# tinyblick.net
KiCad netlist of a schematic drawn in EAGLE
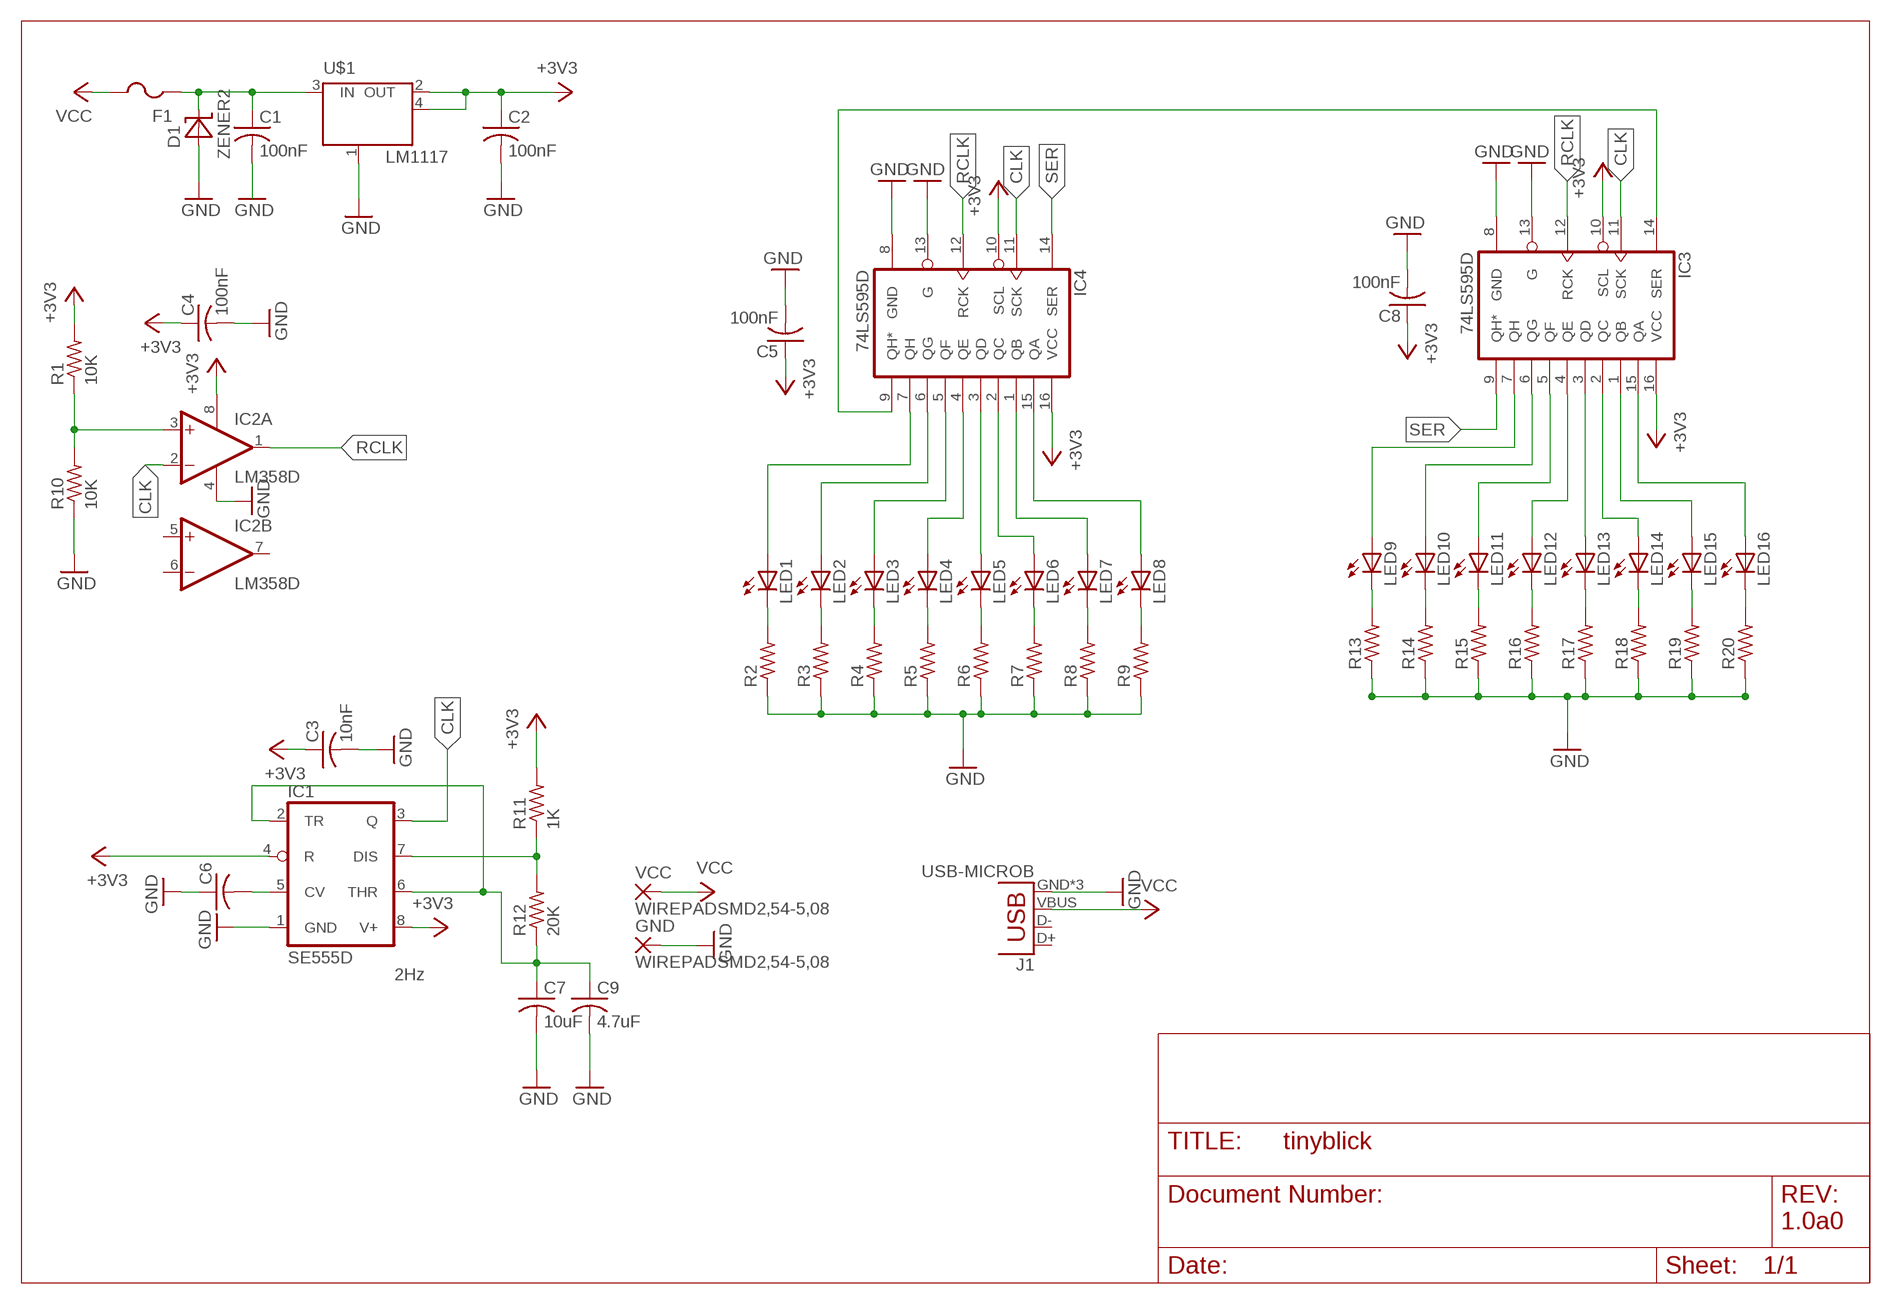
[diagram p0: schematic, sheet 1]

(export (version "E")
  (design (tool "Eeschema 10.0.6"))
  (components
    (comp (ref "C1")
      (value "100nF")
      (footprint "eagle-import:C0603")
      (libsource (lib "eagle-import") (part "C-USC0603"))
    )
    (comp (ref "C2")
      (value "100nF")
      (footprint "eagle-import:C0603")
      (libsource (lib "eagle-import") (part "C-USC0603"))
    )
    (comp (ref "C3")
      (value "10nF")
      (footprint "eagle-import:C0603")
      (libsource (lib "eagle-import") (part "C-USC0603"))
    )
    (comp (ref "C4")
      (value "100nF")
      (footprint "eagle-import:C0603")
      (libsource (lib "eagle-import") (part "C-USC0603"))
    )
    (comp (ref "C5")
      (value "100nF")
      (footprint "eagle-import:C0603")
      (libsource (lib "eagle-import") (part "C-USC0603"))
    )
    (comp (ref "C6")
      (value "C-USC0603")
      (footprint "eagle-import:C0603")
      (libsource (lib "eagle-import") (part "C-USC0603"))
    )
    (comp (ref "C7")
      (value "10uF")
      (footprint "eagle-import:C0603")
      (libsource (lib "eagle-import") (part "C-USC0603"))
    )
    (comp (ref "C8")
      (value "100nF")
      (footprint "eagle-import:C0603")
      (libsource (lib "eagle-import") (part "C-USC0603"))
    )
    (comp (ref "C9")
      (value "4.7uF")
      (footprint "eagle-import:C0603")
      (libsource (lib "eagle-import") (part "C-USC0603"))
    )
    (comp (ref "D1")
      (value "ZENER2")
      (footprint "eagle-import:SOD123")
      (libsource (lib "eagle-import") (part "ZENER2"))
    )
    (comp (ref "F1")
      (value "PTCFUSE-1206")
      (footprint "eagle-import:R1206")
      (libsource (lib "eagle-import") (part "PTCFUSE-1206"))
    )
    (comp (ref "GND")
      (value "WIREPADSMD2,54-5,08")
      (footprint "eagle-import:SMD2,54-5,08")
      (libsource (lib "eagle-import") (part "WIREPADSMD2,54-5,08"))
    )
    (comp (ref "IC1")
      (value "SE555D")
      (footprint "eagle-import:SO08")
      (libsource (lib "eagle-import") (part "555DSE"))
    )
    (comp (ref "IC2")
      (value "LM358D")
      (footprint "eagle-import:SO08")
      (libsource (lib "eagle-import") (part "LM358D"))
    )
    (comp (ref "IC3")
      (value "74LS595D")
      (footprint "eagle-import:SO16")
      (libsource (lib "eagle-import") (part "74595DLS"))
    )
    (comp (ref "IC4")
      (value "74LS595D")
      (footprint "eagle-import:SO16")
      (libsource (lib "eagle-import") (part "74595DLS"))
    )
    (comp (ref "J1")
      (value "USB-MICROB")
      (footprint "eagle-import:USB-MICROB")
      (libsource (lib "eagle-import") (part "USB-MICROB"))
    )
    (comp (ref "LED1")
      (value "LEDCHIP-LED0603")
      (footprint "eagle-import:CHIP-LED0603")
      (libsource (lib "eagle-import") (part "LEDCHIP-LED0603"))
    )
    (comp (ref "LED2")
      (value "LEDCHIP-LED0603")
      (footprint "eagle-import:CHIP-LED0603")
      (libsource (lib "eagle-import") (part "LEDCHIP-LED0603"))
    )
    (comp (ref "LED3")
      (value "LEDCHIP-LED0603")
      (footprint "eagle-import:CHIP-LED0603")
      (libsource (lib "eagle-import") (part "LEDCHIP-LED0603"))
    )
    (comp (ref "LED4")
      (value "LEDCHIP-LED0603")
      (footprint "eagle-import:CHIP-LED0603")
      (libsource (lib "eagle-import") (part "LEDCHIP-LED0603"))
    )
    (comp (ref "LED5")
      (value "LEDCHIP-LED0603")
      (footprint "eagle-import:CHIP-LED0603")
      (libsource (lib "eagle-import") (part "LEDCHIP-LED0603"))
    )
    (comp (ref "LED6")
      (value "LEDCHIP-LED0603")
      (footprint "eagle-import:CHIP-LED0603")
      (libsource (lib "eagle-import") (part "LEDCHIP-LED0603"))
    )
    (comp (ref "LED7")
      (value "LEDCHIP-LED0603")
      (footprint "eagle-import:CHIP-LED0603")
      (libsource (lib "eagle-import") (part "LEDCHIP-LED0603"))
    )
    (comp (ref "LED8")
      (value "LEDCHIP-LED0603")
      (footprint "eagle-import:CHIP-LED0603")
      (libsource (lib "eagle-import") (part "LEDCHIP-LED0603"))
    )
    (comp (ref "LED9")
      (value "LEDCHIP-LED0603")
      (footprint "eagle-import:CHIP-LED0603")
      (libsource (lib "eagle-import") (part "LEDCHIP-LED0603"))
    )
    (comp (ref "LED10")
      (value "LEDCHIP-LED0603")
      (footprint "eagle-import:CHIP-LED0603")
      (libsource (lib "eagle-import") (part "LEDCHIP-LED0603"))
    )
    (comp (ref "LED11")
      (value "LEDCHIP-LED0603")
      (footprint "eagle-import:CHIP-LED0603")
      (libsource (lib "eagle-import") (part "LEDCHIP-LED0603"))
    )
    (comp (ref "LED12")
      (value "LEDCHIP-LED0603")
      (footprint "eagle-import:CHIP-LED0603")
      (libsource (lib "eagle-import") (part "LEDCHIP-LED0603"))
    )
    (comp (ref "LED13")
      (value "LEDCHIP-LED0603")
      (footprint "eagle-import:CHIP-LED0603")
      (libsource (lib "eagle-import") (part "LEDCHIP-LED0603"))
    )
    (comp (ref "LED14")
      (value "LEDCHIP-LED0603")
      (footprint "eagle-import:CHIP-LED0603")
      (libsource (lib "eagle-import") (part "LEDCHIP-LED0603"))
    )
    (comp (ref "LED15")
      (value "LEDCHIP-LED0603")
      (footprint "eagle-import:CHIP-LED0603")
      (libsource (lib "eagle-import") (part "LEDCHIP-LED0603"))
    )
    (comp (ref "LED16")
      (value "LEDCHIP-LED0603")
      (footprint "eagle-import:CHIP-LED0603")
      (libsource (lib "eagle-import") (part "LEDCHIP-LED0603"))
    )
    (comp (ref "R1")
      (value "10K")
      (footprint "eagle-import:R0603")
      (libsource (lib "eagle-import") (part "R-US_R0603"))
    )
    (comp (ref "R2")
      (value "R-US_R0603")
      (footprint "eagle-import:R0603")
      (libsource (lib "eagle-import") (part "R-US_R0603"))
    )
    (comp (ref "R3")
      (value "R-US_R0603")
      (footprint "eagle-import:R0603")
      (libsource (lib "eagle-import") (part "R-US_R0603"))
    )
    (comp (ref "R4")
      (value "R-US_R0603")
      (footprint "eagle-import:R0603")
      (libsource (lib "eagle-import") (part "R-US_R0603"))
    )
    (comp (ref "R5")
      (value "R-US_R0603")
      (footprint "eagle-import:R0603")
      (libsource (lib "eagle-import") (part "R-US_R0603"))
    )
    (comp (ref "R6")
      (value "R-US_R0603")
      (footprint "eagle-import:R0603")
      (libsource (lib "eagle-import") (part "R-US_R0603"))
    )
    (comp (ref "R7")
      (value "R-US_R0603")
      (footprint "eagle-import:R0603")
      (libsource (lib "eagle-import") (part "R-US_R0603"))
    )
    (comp (ref "R8")
      (value "R-US_R0603")
      (footprint "eagle-import:R0603")
      (libsource (lib "eagle-import") (part "R-US_R0603"))
    )
    (comp (ref "R9")
      (value "R-US_R0603")
      (footprint "eagle-import:R0603")
      (libsource (lib "eagle-import") (part "R-US_R0603"))
    )
    (comp (ref "R10")
      (value "10K")
      (footprint "eagle-import:R0603")
      (libsource (lib "eagle-import") (part "R-US_R0603"))
    )
    (comp (ref "R11")
      (value "1K")
      (footprint "eagle-import:R0603")
      (libsource (lib "eagle-import") (part "R-US_R0603"))
    )
    (comp (ref "R12")
      (value "20K")
      (footprint "eagle-import:R0603")
      (libsource (lib "eagle-import") (part "R-US_R0603"))
    )
    (comp (ref "R13")
      (value "R-US_R0603")
      (footprint "eagle-import:R0603")
      (libsource (lib "eagle-import") (part "R-US_R0603"))
    )
    (comp (ref "R14")
      (value "R-US_R0603")
      (footprint "eagle-import:R0603")
      (libsource (lib "eagle-import") (part "R-US_R0603"))
    )
    (comp (ref "R15")
      (value "R-US_R0603")
      (footprint "eagle-import:R0603")
      (libsource (lib "eagle-import") (part "R-US_R0603"))
    )
    (comp (ref "R16")
      (value "R-US_R0603")
      (footprint "eagle-import:R0603")
      (libsource (lib "eagle-import") (part "R-US_R0603"))
    )
    (comp (ref "R17")
      (value "R-US_R0603")
      (footprint "eagle-import:R0603")
      (libsource (lib "eagle-import") (part "R-US_R0603"))
    )
    (comp (ref "R18")
      (value "R-US_R0603")
      (footprint "eagle-import:R0603")
      (libsource (lib "eagle-import") (part "R-US_R0603"))
    )
    (comp (ref "R19")
      (value "R-US_R0603")
      (footprint "eagle-import:R0603")
      (libsource (lib "eagle-import") (part "R-US_R0603"))
    )
    (comp (ref "R20")
      (value "R-US_R0603")
      (footprint "eagle-import:R0603")
      (libsource (lib "eagle-import") (part "R-US_R0603"))
    )
    (comp (ref "U$1")
      (value "LM1117")
      (footprint "eagle-import:SOT223")
      (libsource (lib "eagle-import") (part "LM1117"))
    )
    (comp (ref "VCC")
      (value "WIREPADSMD2,54-5,08")
      (footprint "eagle-import:SMD2,54-5,08")
      (libsource (lib "eagle-import") (part "WIREPADSMD2,54-5,08"))
    )
  )
  (nets
    (net (code "1") (name "+3V3") (class "Default")
      (node (ref "C2") (pin "1") (pinfunction "1_1") (pintype "passive"))
      (node (ref "C3") (pin "1") (pinfunction "1_1") (pintype "passive"))
      (node (ref "C4") (pin "1") (pinfunction "1_1") (pintype "passive"))
      (node (ref "C5") (pin "1") (pinfunction "1_1") (pintype "passive"))
      (node (ref "C8") (pin "1") (pinfunction "1_1") (pintype "passive"))
      (node (ref "IC1") (pin "4") (pinfunction "R_4") (pintype "input"))
      (node (ref "IC1") (pin "8") (pinfunction "V+_8") (pintype "power_in"))
      (node (ref "IC2") (pin "8") (pinfunction "V+_8") (pintype "power_in"))
      (node (ref "IC3") (pin "10") (pinfunction "SCL_10") (pintype "input"))
      (node (ref "IC3") (pin "16") (pinfunction "VCC_16") (pintype "power_in"))
      (node (ref "IC4") (pin "10") (pinfunction "SCL_10") (pintype "input"))
      (node (ref "IC4") (pin "16") (pinfunction "VCC_16") (pintype "power_in"))
      (node (ref "R1") (pin "2") (pinfunction "2_2") (pintype "passive"))
      (node (ref "R11") (pin "2") (pinfunction "2_2") (pintype "passive"))
      (node (ref "U$1") (pin "2") (pinfunction "OUT_2") (pintype "passive"))
      (node (ref "U$1") (pin "4") (pinfunction "OUT_4") (pintype "passive"))
    )
    (net (code "2") (name "CLK") (class "Default")
      (node (ref "IC1") (pin "3") (pinfunction "Q_3") (pintype "output"))
      (node (ref "IC2") (pin "2") (pinfunction "-IN_2") (pintype "input"))
      (node (ref "IC3") (pin "11") (pinfunction "SCK_11") (pintype "input"))
      (node (ref "IC4") (pin "11") (pinfunction "SCK_11") (pintype "input"))
    )
    (net (code "3") (name "GND") (class "Default")
      (node (ref "C1") (pin "2") (pinfunction "2_2") (pintype "passive"))
      (node (ref "C2") (pin "2") (pinfunction "2_2") (pintype "passive"))
      (node (ref "C3") (pin "2") (pinfunction "2_2") (pintype "passive"))
      (node (ref "C4") (pin "2") (pinfunction "2_2") (pintype "passive"))
      (node (ref "C5") (pin "2") (pinfunction "2_2") (pintype "passive"))
      (node (ref "C6") (pin "1") (pinfunction "1_1") (pintype "passive"))
      (node (ref "C7") (pin "2") (pinfunction "2_2") (pintype "passive"))
      (node (ref "C8") (pin "2") (pinfunction "2_2") (pintype "passive"))
      (node (ref "C9") (pin "2") (pinfunction "2_2") (pintype "passive"))
      (node (ref "D1") (pin "A") (pinfunction "A_A") (pintype "passive"))
      (node (ref "GND") (pin "1") (pinfunction "P_1") (pintype "passive"))
      (node (ref "IC1") (pin "1") (pinfunction "GND_1") (pintype "power_in"))
      (node (ref "IC2") (pin "4") (pinfunction "V-_4") (pintype "power_in"))
      (node (ref "IC3") (pin "13") (pinfunction "G_13") (pintype "input"))
      (node (ref "IC3") (pin "8") (pinfunction "GND_8") (pintype "power_in"))
      (node (ref "IC4") (pin "13") (pinfunction "G_13") (pintype "input"))
      (node (ref "IC4") (pin "8") (pinfunction "GND_8") (pintype "power_in"))
      (node (ref "J1") (pin "GND") (pinfunction "GND_GND") (pintype "bidirectional"))
      (node (ref "J1") (pin "MT1") (pinfunction "GND_MT1") (pintype "bidirectional"))
      (node (ref "J1") (pin "MT2") (pinfunction "GND_MT2") (pintype "bidirectional"))
      (node (ref "R10") (pin "1") (pinfunction "1_1") (pintype "passive"))
      (node (ref "R13") (pin "1") (pinfunction "1_1") (pintype "passive"))
      (node (ref "R14") (pin "1") (pinfunction "1_1") (pintype "passive"))
      (node (ref "R15") (pin "1") (pinfunction "1_1") (pintype "passive"))
      (node (ref "R16") (pin "1") (pinfunction "1_1") (pintype "passive"))
      (node (ref "R17") (pin "1") (pinfunction "1_1") (pintype "passive"))
      (node (ref "R18") (pin "1") (pinfunction "1_1") (pintype "passive"))
      (node (ref "R19") (pin "1") (pinfunction "1_1") (pintype "passive"))
      (node (ref "R2") (pin "1") (pinfunction "1_1") (pintype "passive"))
      (node (ref "R20") (pin "1") (pinfunction "1_1") (pintype "passive"))
      (node (ref "R3") (pin "1") (pinfunction "1_1") (pintype "passive"))
      (node (ref "R4") (pin "1") (pinfunction "1_1") (pintype "passive"))
      (node (ref "R5") (pin "1") (pinfunction "1_1") (pintype "passive"))
      (node (ref "R6") (pin "1") (pinfunction "1_1") (pintype "passive"))
      (node (ref "R7") (pin "1") (pinfunction "1_1") (pintype "passive"))
      (node (ref "R8") (pin "1") (pinfunction "1_1") (pintype "passive"))
      (node (ref "R9") (pin "1") (pinfunction "1_1") (pintype "passive"))
      (node (ref "U$1") (pin "1") (pinfunction "GND/ADJ_1") (pintype "input"))
    )
    (net (code "4") (name "Net-(IC1-CV)") (class "Default")
      (node (ref "C6") (pin "2") (pinfunction "2_2") (pintype "passive"))
      (node (ref "IC1") (pin "5") (pinfunction "CV_5") (pintype "input"))
    )
    (net (code "5") (name "Net-(IC1-DIS)") (class "Default")
      (node (ref "IC1") (pin "7") (pinfunction "DIS_7") (pintype "input"))
      (node (ref "R11") (pin "1") (pinfunction "1_1") (pintype "passive"))
      (node (ref "R12") (pin "2") (pinfunction "2_2") (pintype "passive"))
    )
    (net (code "6") (name "Net-(IC1-THR)") (class "Default")
      (node (ref "C7") (pin "1") (pinfunction "1_1") (pintype "passive"))
      (node (ref "C9") (pin "1") (pinfunction "1_1") (pintype "passive"))
      (node (ref "IC1") (pin "2") (pinfunction "TR_2") (pintype "input"))
      (node (ref "IC1") (pin "6") (pinfunction "THR_6") (pintype "input"))
      (node (ref "R12") (pin "1") (pinfunction "1_1") (pintype "passive"))
    )
    (net (code "7") (name "Net-(IC2A-+IN)") (class "Default")
      (node (ref "IC2") (pin "3") (pinfunction "+IN_3") (pintype "input"))
      (node (ref "R1") (pin "1") (pinfunction "1_1") (pintype "passive"))
      (node (ref "R10") (pin "2") (pinfunction "2_2") (pintype "passive"))
    )
    (net (code "8") (name "Net-(IC3-QA)") (class "Default")
      (node (ref "IC3") (pin "15") (pinfunction "QA_15") (pintype "tri_state"))
      (node (ref "LED16") (pin "A") (pinfunction "A_A") (pintype "passive"))
    )
    (net (code "9") (name "Net-(IC3-QB)") (class "Default")
      (node (ref "IC3") (pin "1") (pinfunction "QB_1") (pintype "tri_state"))
      (node (ref "LED15") (pin "A") (pinfunction "A_A") (pintype "passive"))
    )
    (net (code "10") (name "Net-(IC3-QC)") (class "Default")
      (node (ref "IC3") (pin "2") (pinfunction "QC_2") (pintype "tri_state"))
      (node (ref "LED14") (pin "A") (pinfunction "A_A") (pintype "passive"))
    )
    (net (code "11") (name "Net-(IC3-QD)") (class "Default")
      (node (ref "IC3") (pin "3") (pinfunction "QD_3") (pintype "tri_state"))
      (node (ref "LED13") (pin "A") (pinfunction "A_A") (pintype "passive"))
    )
    (net (code "12") (name "Net-(IC3-QE)") (class "Default")
      (node (ref "IC3") (pin "4") (pinfunction "QE_4") (pintype "tri_state"))
      (node (ref "LED12") (pin "A") (pinfunction "A_A") (pintype "passive"))
    )
    (net (code "13") (name "Net-(IC3-QF)") (class "Default")
      (node (ref "IC3") (pin "5") (pinfunction "QF_5") (pintype "tri_state"))
      (node (ref "LED11") (pin "A") (pinfunction "A_A") (pintype "passive"))
    )
    (net (code "14") (name "Net-(IC3-QG)") (class "Default")
      (node (ref "IC3") (pin "6") (pinfunction "QG_6") (pintype "tri_state"))
      (node (ref "LED10") (pin "A") (pinfunction "A_A") (pintype "passive"))
    )
    (net (code "15") (name "Net-(IC3-QH)") (class "Default")
      (node (ref "IC3") (pin "7") (pinfunction "QH_7") (pintype "tri_state"))
      (node (ref "LED9") (pin "A") (pinfunction "A_A") (pintype "passive"))
    )
    (net (code "16") (name "Net-(IC3-SER)") (class "Default")
      (node (ref "IC3") (pin "14") (pinfunction "SER_14") (pintype "input"))
      (node (ref "IC4") (pin "9") (pinfunction "QH*_9") (pintype "tri_state"))
    )
    (net (code "17") (name "Net-(IC4-QA)") (class "Default")
      (node (ref "IC4") (pin "15") (pinfunction "QA_15") (pintype "tri_state"))
      (node (ref "LED8") (pin "A") (pinfunction "A_A") (pintype "passive"))
    )
    (net (code "18") (name "Net-(IC4-QB)") (class "Default")
      (node (ref "IC4") (pin "1") (pinfunction "QB_1") (pintype "tri_state"))
      (node (ref "LED7") (pin "A") (pinfunction "A_A") (pintype "passive"))
    )
    (net (code "19") (name "Net-(IC4-QC)") (class "Default")
      (node (ref "IC4") (pin "2") (pinfunction "QC_2") (pintype "tri_state"))
      (node (ref "LED6") (pin "A") (pinfunction "A_A") (pintype "passive"))
    )
    (net (code "20") (name "Net-(IC4-QD)") (class "Default")
      (node (ref "IC4") (pin "3") (pinfunction "QD_3") (pintype "tri_state"))
      (node (ref "LED5") (pin "A") (pinfunction "A_A") (pintype "passive"))
    )
    (net (code "21") (name "Net-(IC4-QE)") (class "Default")
      (node (ref "IC4") (pin "4") (pinfunction "QE_4") (pintype "tri_state"))
      (node (ref "LED4") (pin "A") (pinfunction "A_A") (pintype "passive"))
    )
    (net (code "22") (name "Net-(IC4-QF)") (class "Default")
      (node (ref "IC4") (pin "5") (pinfunction "QF_5") (pintype "tri_state"))
      (node (ref "LED3") (pin "A") (pinfunction "A_A") (pintype "passive"))
    )
    (net (code "23") (name "Net-(IC4-QG)") (class "Default")
      (node (ref "IC4") (pin "6") (pinfunction "QG_6") (pintype "tri_state"))
      (node (ref "LED2") (pin "A") (pinfunction "A_A") (pintype "passive"))
    )
    (net (code "24") (name "Net-(IC4-QH)") (class "Default")
      (node (ref "IC4") (pin "7") (pinfunction "QH_7") (pintype "tri_state"))
      (node (ref "LED1") (pin "A") (pinfunction "A_A") (pintype "passive"))
    )
    (net (code "25") (name "Net-(LED1-PadC)") (class "Default")
      (node (ref "LED1") (pin "C") (pinfunction "C_C") (pintype "passive"))
      (node (ref "R2") (pin "2") (pinfunction "2_2") (pintype "passive"))
    )
    (net (code "26") (name "Net-(LED2-PadC)") (class "Default")
      (node (ref "LED2") (pin "C") (pinfunction "C_C") (pintype "passive"))
      (node (ref "R3") (pin "2") (pinfunction "2_2") (pintype "passive"))
    )
    (net (code "27") (name "Net-(LED3-PadC)") (class "Default")
      (node (ref "LED3") (pin "C") (pinfunction "C_C") (pintype "passive"))
      (node (ref "R4") (pin "2") (pinfunction "2_2") (pintype "passive"))
    )
    (net (code "28") (name "Net-(LED4-PadC)") (class "Default")
      (node (ref "LED4") (pin "C") (pinfunction "C_C") (pintype "passive"))
      (node (ref "R5") (pin "2") (pinfunction "2_2") (pintype "passive"))
    )
    (net (code "29") (name "Net-(LED5-PadC)") (class "Default")
      (node (ref "LED5") (pin "C") (pinfunction "C_C") (pintype "passive"))
      (node (ref "R6") (pin "2") (pinfunction "2_2") (pintype "passive"))
    )
    (net (code "30") (name "Net-(LED6-PadC)") (class "Default")
      (node (ref "LED6") (pin "C") (pinfunction "C_C") (pintype "passive"))
      (node (ref "R7") (pin "2") (pinfunction "2_2") (pintype "passive"))
    )
    (net (code "31") (name "Net-(LED7-PadC)") (class "Default")
      (node (ref "LED7") (pin "C") (pinfunction "C_C") (pintype "passive"))
      (node (ref "R8") (pin "2") (pinfunction "2_2") (pintype "passive"))
    )
    (net (code "32") (name "Net-(LED8-PadC)") (class "Default")
      (node (ref "LED8") (pin "C") (pinfunction "C_C") (pintype "passive"))
      (node (ref "R9") (pin "2") (pinfunction "2_2") (pintype "passive"))
    )
    (net (code "33") (name "Net-(LED9-PadC)") (class "Default")
      (node (ref "LED9") (pin "C") (pinfunction "C_C") (pintype "passive"))
      (node (ref "R13") (pin "2") (pinfunction "2_2") (pintype "passive"))
    )
    (net (code "34") (name "Net-(LED10-PadC)") (class "Default")
      (node (ref "LED10") (pin "C") (pinfunction "C_C") (pintype "passive"))
      (node (ref "R14") (pin "2") (pinfunction "2_2") (pintype "passive"))
    )
    (net (code "35") (name "Net-(LED11-PadC)") (class "Default")
      (node (ref "LED11") (pin "C") (pinfunction "C_C") (pintype "passive"))
      (node (ref "R15") (pin "2") (pinfunction "2_2") (pintype "passive"))
    )
    (net (code "36") (name "Net-(LED12-PadC)") (class "Default")
      (node (ref "LED12") (pin "C") (pinfunction "C_C") (pintype "passive"))
      (node (ref "R16") (pin "2") (pinfunction "2_2") (pintype "passive"))
    )
    (net (code "37") (name "Net-(LED13-PadC)") (class "Default")
      (node (ref "LED13") (pin "C") (pinfunction "C_C") (pintype "passive"))
      (node (ref "R17") (pin "2") (pinfunction "2_2") (pintype "passive"))
    )
    (net (code "38") (name "Net-(LED14-PadC)") (class "Default")
      (node (ref "LED14") (pin "C") (pinfunction "C_C") (pintype "passive"))
      (node (ref "R18") (pin "2") (pinfunction "2_2") (pintype "passive"))
    )
    (net (code "39") (name "Net-(LED15-PadC)") (class "Default")
      (node (ref "LED15") (pin "C") (pinfunction "C_C") (pintype "passive"))
      (node (ref "R19") (pin "2") (pinfunction "2_2") (pintype "passive"))
    )
    (net (code "40") (name "Net-(LED16-PadC)") (class "Default")
      (node (ref "LED16") (pin "C") (pinfunction "C_C") (pintype "passive"))
      (node (ref "R20") (pin "2") (pinfunction "2_2") (pintype "passive"))
    )
    (net (code "41") (name "Net-(U$1-IN)") (class "Default")
      (node (ref "C1") (pin "1") (pinfunction "1_1") (pintype "passive"))
      (node (ref "D1") (pin "C") (pinfunction "C_C") (pintype "passive"))
      (node (ref "F1") (pin "1") (pinfunction "1_1") (pintype "passive"))
      (node (ref "U$1") (pin "3") (pinfunction "IN_3") (pintype "input"))
    )
    (net (code "42") (name "RCLK") (class "Default")
      (node (ref "IC2") (pin "1") (pinfunction "OUT_1") (pintype "output"))
      (node (ref "IC3") (pin "12") (pinfunction "RCK_12") (pintype "input"))
      (node (ref "IC4") (pin "12") (pinfunction "RCK_12") (pintype "input"))
    )
    (net (code "43") (name "SER") (class "Default")
      (node (ref "IC3") (pin "9") (pinfunction "QH*_9") (pintype "tri_state"))
      (node (ref "IC4") (pin "14") (pinfunction "SER_14") (pintype "input"))
    )
    (net (code "44") (name "VCC") (class "Default")
      (node (ref "F1") (pin "2") (pinfunction "2_2") (pintype "passive"))
      (node (ref "J1") (pin "VBUS") (pinfunction "VBUS_VBUS") (pintype "bidirectional"))
      (node (ref "VCC") (pin "1") (pinfunction "P_1") (pintype "passive"))
    )
    (net (code "45") (name "unconnected-(IC2B-+IN-Pad5)") (class "Default")
      (node (ref "IC2") (pin "5") (pinfunction "+IN_5") (pintype "input"))
    )
    (net (code "46") (name "unconnected-(IC2B--IN-Pad6)") (class "Default")
      (node (ref "IC2") (pin "6") (pinfunction "-IN_6") (pintype "input"))
    )
    (net (code "47") (name "unconnected-(IC2B-OUT-Pad7)") (class "Default")
      (node (ref "IC2") (pin "7") (pinfunction "OUT_7") (pintype "output"))
    )
    (net (code "48") (name "unconnected-(J1-PadD+)") (class "Default")
      (node (ref "J1") (pin "D+") (pinfunction "D+_D+") (pintype "bidirectional"))
    )
    (net (code "49") (name "unconnected-(J1-PadD-)") (class "Default")
      (node (ref "J1") (pin "D-") (pinfunction "D-_D-") (pintype "bidirectional"))
    )
  )
)
